# VREG_AOZ1284PI_3V3_4A.net
KiCad netlist of a schematic drawn in Altium Designer
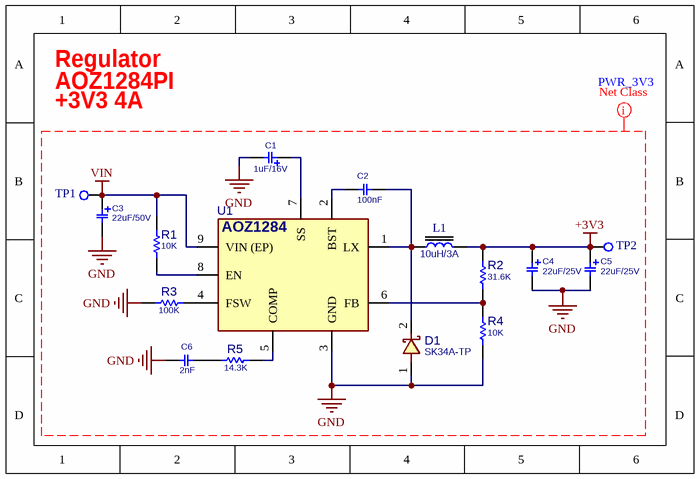
[diagram p0: VREG AOZ1284PI +3V3 4A.SchDoc]

(export (version "E")
  (design (tool "Eeschema 10.0.6"))
  (components
    (comp (ref "C1")
      (value "1uF/16V")
      (footprint "C_TN_A")
      (description "CAP, SMD, TAN")
      (libsource (lib "Passive") (part "CAP_SMD_TAN"))
    )
    (comp (ref "C2")
      (value "100nF")
      (footprint "C0603S")
      (description "CAP, SMD, MLCC")
      (fields (field (name "MANF_P#") "MANF_PART#") (field (name "MANF") "Murata"))
      (libsource (lib "Passive") (part "CAP_SMD_MLCC"))
    )
    (comp (ref "C3")
      (value "22uF/50V")
      (footprint "C_TN_A")
      (description "CAP, SMD, TAN")
      (libsource (lib "Passive") (part "CAP_SMD_TAN"))
    )
    (comp (ref "C4")
      (value "22uF/25V")
      (footprint "C_TN_A")
      (description "CAP, SMD, TAN")
      (libsource (lib "Passive") (part "CAP_SMD_TAN"))
    )
    (comp (ref "C5")
      (value "22uF/25V")
      (footprint "C_TN_A")
      (description "CAP, SMD, TAN")
      (libsource (lib "Passive") (part "CAP_SMD_TAN"))
    )
    (comp (ref "C6")
      (value "2nF")
      (footprint "C0603S")
      (description "CAP, SMD, MLCC")
      (fields (field (name "MANF_P#") "MANF_PART#") (field (name "MANF") "Murata"))
      (libsource (lib "Passive") (part "CAP_SMD_MLCC"))
    )
    (comp (ref "D1")
      (value "SK34A-TP")
      (footprint "D_SMA")
      (description "DIODE, SCHOTTKY, 40V, 3A")
      (fields (field (name "MANF") "Vishay") (field (name "MANF_P#") "SS14-E3"))
      (libsource (lib "PW Components 97_492") (part "DIODE_SMD_SCHOTTKY_SK34A-TP"))
    )
    (comp (ref "L1")
      (value "10uH/3A")
      (footprint "L_8X8")
      (description "IND, PWR, SMD")
      (libsource (lib "Passive") (part "INDPWR_SMD"))
    )
    (comp (ref "R1")
      (value "10K")
      (footprint "R0603S")
      (description "RES, SMD")
      (fields (field (name "MANF_P#") "RK73H1ETTP4701F") (field (name "MANF") "KOA SPEER"))
      (libsource (lib "Passive") (part "RES_SMD"))
    )
    (comp (ref "R2")
      (value "31.6K")
      (footprint "R0603S")
      (description "RES, SMD")
      (fields (field (name "MANF_P#") "RK73H1ETTP4701F") (field (name "MANF") "KOA SPEER"))
      (libsource (lib "Passive") (part "RES_SMD"))
    )
    (comp (ref "R3")
      (value "100K")
      (footprint "R0603S")
      (description "RES, SMD")
      (fields (field (name "MANF_P#") "RK73H1ETTP4701F") (field (name "MANF") "KOA SPEER"))
      (libsource (lib "Passive") (part "RES_SMD"))
    )
    (comp (ref "R4")
      (value "10K")
      (footprint "R0603S")
      (description "RES, SMD")
      (fields (field (name "MANF_P#") "RK73H1ETTP4701F") (field (name "MANF") "KOA SPEER"))
      (libsource (lib "Passive") (part "RES_SMD"))
    )
    (comp (ref "R5")
      (value "14.3K")
      (footprint "R0603S")
      (description "RES, SMD")
      (fields (field (name "MANF_P#") "RK73H1ETTP4701F") (field (name "MANF") "KOA SPEER"))
      (libsource (lib "Passive") (part "RES_SMD"))
    )
    (comp (ref "TP1")
      (value "Test Point")
      (footprint "TPSMD_C1")
      (libsource (lib "PW Components") (part "Test Point"))
    )
    (comp (ref "TP2")
      (value "Test Point")
      (footprint "TPSMD_C1")
      (libsource (lib "PW Components") (part "Test Point"))
    )
    (comp (ref "U1")
      (value "AOZ1021AI")
      (footprint "SO_8T")
      (description "REG, Switching, Buck, 4A, ADJ, 500KHz, 3~36VIN, SO-8")
      (fields (field (name "MANF") "AOSMD"))
      (libsource (lib "PW Components 97_492") (part "VREG_AOZ1284PI_SO8"))
    )
  )
  (nets
    (net (code "1") (name "+3V3") (class "Default")
      (node (ref "C4") (pin "1") (pinfunction "1_1") (pintype "passive"))
      (node (ref "C5") (pin "1") (pinfunction "1_1") (pintype "passive"))
      (node (ref "L1") (pin "2") (pinfunction "2_2") (pintype "passive"))
      (node (ref "R2") (pin "1") (pinfunction "1_1") (pintype "passive"))
      (node (ref "TP2") (pin "1") (pinfunction "TP_1") (pintype "passive"))
    )
    (net (code "2") (name "GND") (class "Default")
      (node (ref "C1") (pin "2") (pinfunction "2_2") (pintype "passive"))
      (node (ref "C3") (pin "2") (pinfunction "2_2") (pintype "passive"))
      (node (ref "C4") (pin "2") (pinfunction "2_2") (pintype "passive"))
      (node (ref "C5") (pin "2") (pinfunction "2_2") (pintype "passive"))
      (node (ref "C6") (pin "2") (pinfunction "2_2") (pintype "passive"))
      (node (ref "D1") (pin "1") (pinfunction "1_1") (pintype "passive"))
      (node (ref "R3") (pin "1") (pinfunction "1_1") (pintype "passive"))
      (node (ref "R4") (pin "2") (pinfunction "2_2") (pintype "passive"))
      (node (ref "U1") (pin "3") (pinfunction "GND_3") (pintype "power_in"))
    )
    (net (code "3") (name "Net-(C6-Pad1)") (class "Default")
      (node (ref "C6") (pin "1") (pinfunction "1_1") (pintype "passive"))
      (node (ref "R5") (pin "1") (pinfunction "1_1") (pintype "passive"))
    )
    (net (code "4") (name "Net-(U1-BST)") (class "Default")
      (node (ref "C2") (pin "2") (pinfunction "2_2") (pintype "passive"))
      (node (ref "U1") (pin "2") (pinfunction "BST_2") (pintype "passive"))
    )
    (net (code "5") (name "Net-(U1-COMP)") (class "Default")
      (node (ref "R5") (pin "2") (pinfunction "2_2") (pintype "passive"))
      (node (ref "U1") (pin "5") (pinfunction "COMP_5") (pintype "power_in"))
    )
    (net (code "6") (name "Net-(U1-EN)") (class "Default")
      (node (ref "R1") (pin "2") (pinfunction "2_2") (pintype "passive"))
      (node (ref "U1") (pin "8") (pinfunction "EN_8") (pintype "passive"))
    )
    (net (code "7") (name "Net-(U1-FB)") (class "Default")
      (node (ref "R2") (pin "2") (pinfunction "2_2") (pintype "passive"))
      (node (ref "R4") (pin "1") (pinfunction "1_1") (pintype "passive"))
      (node (ref "U1") (pin "6") (pinfunction "FB_6") (pintype "passive"))
    )
    (net (code "8") (name "Net-(U1-FSW)") (class "Default")
      (node (ref "R3") (pin "2") (pinfunction "2_2") (pintype "passive"))
      (node (ref "U1") (pin "4") (pinfunction "FSW_4") (pintype "passive"))
    )
    (net (code "9") (name "Net-(U1-LX)") (class "Default")
      (node (ref "C2") (pin "1") (pinfunction "1_1") (pintype "passive"))
      (node (ref "D1") (pin "2") (pinfunction "2_2") (pintype "passive"))
      (node (ref "L1") (pin "1") (pinfunction "1_1") (pintype "passive"))
      (node (ref "U1") (pin "1") (pinfunction "LX_1") (pintype "passive"))
    )
    (net (code "10") (name "Net-(U1-SS)") (class "Default")
      (node (ref "C1") (pin "1") (pinfunction "1_1") (pintype "passive"))
      (node (ref "U1") (pin "7") (pinfunction "SS_7") (pintype "passive"))
    )
    (net (code "11") (name "VIN") (class "Default")
      (node (ref "C3") (pin "1") (pinfunction "1_1") (pintype "passive"))
      (node (ref "R1") (pin "1") (pinfunction "1_1") (pintype "passive"))
      (node (ref "TP1") (pin "1") (pinfunction "TP_1") (pintype "passive"))
      (node (ref "U1") (pin "9") (pinfunction "VIN_(EP)_9") (pintype "power_in"))
    )
  )
)
